# Tiefenentladeschutz.net
KiCad netlist of a schematic drawn in EAGLE
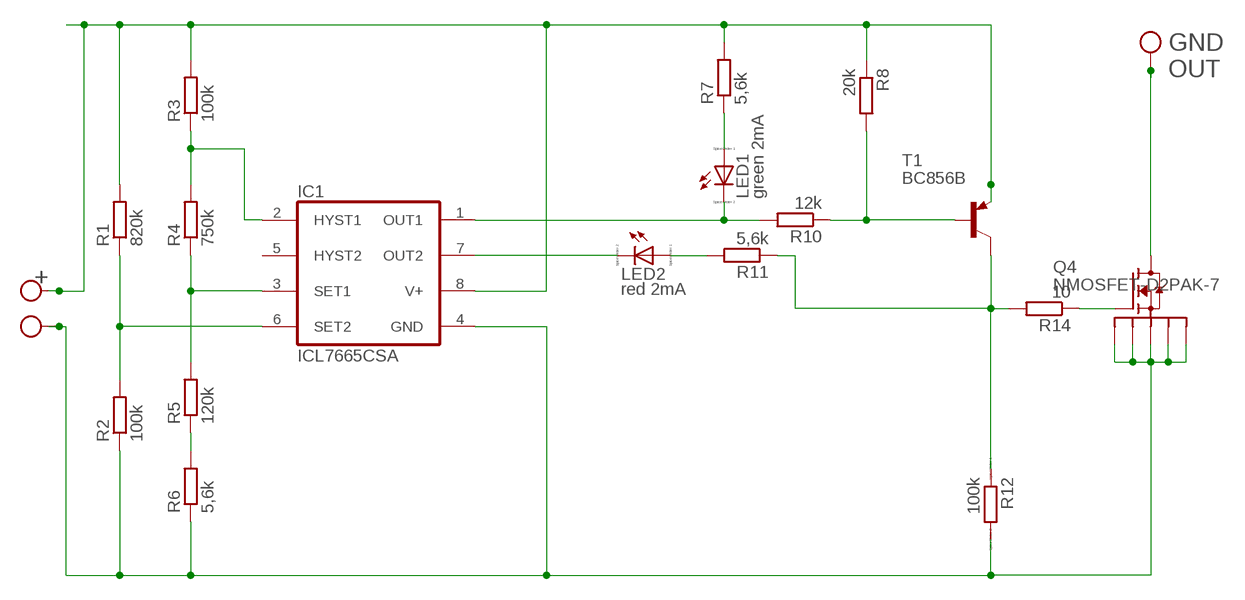
[diagram p0: schematic, sheet 1]

(export (version "E")
  (design (tool "Eeschema 10.0.6"))
  (components
    (comp (ref "IC1")
      (value "ICL7665CSA")
      (footprint "eagle-import:SO08")
      (fields (field (name "MPN") "ICL7665CSA+"))
      (libsource (lib "eagle-import") (part "ICL7665CSA"))
    )
    (comp (ref "LED1")
      (value "green 2mA")
      (footprint "eagle-import:LED_SML0603")
      (libsource (lib "eagle-import") (part "LED_ESML0603"))
    )
    (comp (ref "LED2")
      (value "red 2mA")
      (footprint "eagle-import:LED_SML0603")
      (libsource (lib "eagle-import") (part "LED_ESML0603"))
    )
    (comp (ref "Q4")
      (value "NMOSFET-D2PAK-7")
      (footprint "eagle-import:H2PAK-6")
      (libsource (lib "eagle-import") (part "NMOSFET-D2PAK-7"))
    )
    (comp (ref "R1")
      (value "820k")
      (footprint "eagle-import:R0603")
      (libsource (lib "eagle-import") (part "resistor_R-EU_R0603"))
    )
    (comp (ref "R2")
      (value "100k")
      (footprint "eagle-import:R0603")
      (libsource (lib "eagle-import") (part "resistor_R-EU_R0603"))
    )
    (comp (ref "R3")
      (value "100k")
      (footprint "eagle-import:M1206")
      (libsource (lib "eagle-import") (part "R-EU_M1206"))
    )
    (comp (ref "R4")
      (value "750k")
      (footprint "eagle-import:R0603")
      (libsource (lib "eagle-import") (part "R-EU_R0603"))
    )
    (comp (ref "R5")
      (value "120k")
      (footprint "eagle-import:R0603")
      (libsource (lib "eagle-import") (part "R-EU_R0603"))
    )
    (comp (ref "R6")
      (value "5,6k")
      (footprint "eagle-import:R0603")
      (libsource (lib "eagle-import") (part "R-EU_R0603"))
    )
    (comp (ref "R7")
      (value "5,6k")
      (footprint "eagle-import:R0603")
      (libsource (lib "eagle-import") (part "R-EU_R0603"))
    )
    (comp (ref "R8")
      (value "20k")
      (footprint "eagle-import:R0603")
      (libsource (lib "eagle-import") (part "R-EU_R0603"))
    )
    (comp (ref "R10")
      (value "12k")
      (footprint "eagle-import:R0603")
      (libsource (lib "eagle-import") (part "R-EU_R0603"))
    )
    (comp (ref "R11")
      (value "5,6k")
      (footprint "eagle-import:R0603")
      (libsource (lib "eagle-import") (part "R-EU_R0603"))
    )
    (comp (ref "R12")
      (value "100k")
      (footprint "eagle-import:R1206")
      (libsource (lib "eagle-import") (part "RR1206"))
    )
    (comp (ref "R14")
      (value "10")
      (footprint "eagle-import:R0603")
      (libsource (lib "eagle-import") (part "R-EU_R0603"))
    )
    (comp (ref "T1")
      (value "BC856B")
      (footprint "eagle-import:SOT23-BEC")
      (libsource (lib "eagle-import") (part "-PNP-SOT23-BECBC856B"))
    )
    (comp (ref "U$4")
      (value "PIN2.54")
      (footprint "eagle-import:PIN")
      (libsource (lib "eagle-import") (part "PIN2.54"))
    )
    (comp (ref "U$6")
      (value "PIN1.27")
      (footprint "eagle-import:PIN-1.27")
      (libsource (lib "eagle-import") (part "PIN1.27"))
    )
    (comp (ref "U$7")
      (value "PIN1.27")
      (footprint "eagle-import:PIN-1.27")
      (libsource (lib "eagle-import") (part "PIN1.27"))
    )
  )
  (nets
    (net (code "1") (name "Net-(IC1-GND)") (class "Default")
      (node (ref "IC1") (pin "4") (pinfunction "GND_4") (pintype "power_in"))
      (node (ref "Q4") (pin "S1") (pinfunction "S1_S1") (pintype "passive"))
      (node (ref "Q4") (pin "S2") (pinfunction "S2_S2") (pintype "passive"))
      (node (ref "Q4") (pin "S3") (pinfunction "S3_S3") (pintype "passive"))
      (node (ref "Q4") (pin "S4") (pinfunction "S4_S4") (pintype "passive"))
      (node (ref "Q4") (pin "S5") (pinfunction "S5_S5") (pintype "passive"))
      (node (ref "R12") (pin "2") (pinfunction "2_2") (pintype "passive"))
      (node (ref "R2") (pin "1") (pinfunction "1_1") (pintype "passive"))
      (node (ref "R6") (pin "1") (pinfunction "1_1") (pintype "passive"))
      (node (ref "U$6") (pin "P$1") (pinfunction "P$1_P$1") (pintype "bidirectional"))
    )
    (net (code "2") (name "Net-(IC1-HYST1)") (class "Default")
      (node (ref "IC1") (pin "2") (pinfunction "HYST1_2") (pintype "input"))
      (node (ref "R3") (pin "1") (pinfunction "1_1") (pintype "passive"))
      (node (ref "R4") (pin "2") (pinfunction "2_2") (pintype "passive"))
    )
    (net (code "3") (name "Net-(IC1-OUT1)") (class "Default")
      (node (ref "IC1") (pin "1") (pinfunction "OUT1_1") (pintype "output"))
      (node (ref "LED1") (pin "C") (pinfunction "C_C") (pintype "passive"))
      (node (ref "R10") (pin "2") (pinfunction "2_2") (pintype "passive"))
    )
    (net (code "4") (name "Net-(IC1-OUT2)") (class "Default")
      (node (ref "IC1") (pin "7") (pinfunction "OUT2_7") (pintype "output"))
      (node (ref "LED2") (pin "C") (pinfunction "C_C") (pintype "passive"))
    )
    (net (code "5") (name "Net-(IC1-SET1)") (class "Default")
      (node (ref "IC1") (pin "3") (pinfunction "SET1_3") (pintype "input"))
      (node (ref "R4") (pin "1") (pinfunction "1_1") (pintype "passive"))
      (node (ref "R5") (pin "2") (pinfunction "2_2") (pintype "passive"))
    )
    (net (code "6") (name "Net-(IC1-SET2)") (class "Default")
      (node (ref "IC1") (pin "6") (pinfunction "SET2_6") (pintype "input"))
      (node (ref "R1") (pin "1") (pinfunction "1_1") (pintype "passive"))
      (node (ref "R2") (pin "2") (pinfunction "2_2") (pintype "passive"))
    )
    (net (code "7") (name "Net-(IC1-V+)") (class "Default")
      (node (ref "IC1") (pin "8") (pinfunction "V+_8") (pintype "power_in"))
      (node (ref "R1") (pin "2") (pinfunction "2_2") (pintype "passive"))
      (node (ref "R3") (pin "2") (pinfunction "2_2") (pintype "passive"))
      (node (ref "R7") (pin "2") (pinfunction "2_2") (pintype "passive"))
      (node (ref "R8") (pin "1") (pinfunction "1_1") (pintype "passive"))
      (node (ref "T1") (pin "E") (pinfunction "E_E") (pintype "passive"))
      (node (ref "U$4") (pin "P$1") (pinfunction "P$1_P$1") (pintype "bidirectional"))
    )
    (net (code "8") (name "Net-(LED1-PadA)") (class "Default")
      (node (ref "LED1") (pin "A") (pinfunction "A_A") (pintype "passive"))
      (node (ref "R7") (pin "1") (pinfunction "1_1") (pintype "passive"))
    )
    (net (code "9") (name "Net-(LED2-PadA)") (class "Default")
      (node (ref "LED2") (pin "A") (pinfunction "A_A") (pintype "passive"))
      (node (ref "R11") (pin "2") (pinfunction "2_2") (pintype "passive"))
    )
    (net (code "10") (name "Net-(Q4-PadD)") (class "Default")
      (node (ref "Q4") (pin "D") (pinfunction "D_D") (pintype "passive"))
      (node (ref "U$7") (pin "P$1") (pinfunction "P$1_P$1") (pintype "bidirectional"))
    )
    (net (code "11") (name "Net-(Q4-PadG)") (class "Default")
      (node (ref "Q4") (pin "G") (pinfunction "G_G") (pintype "passive"))
      (node (ref "R14") (pin "1") (pinfunction "1_1") (pintype "passive"))
    )
    (net (code "12") (name "Net-(R5-Pad1)") (class "Default")
      (node (ref "R5") (pin "1") (pinfunction "1_1") (pintype "passive"))
      (node (ref "R6") (pin "2") (pinfunction "2_2") (pintype "passive"))
    )
    (net (code "13") (name "Net-(R10-Pad1)") (class "Default")
      (node (ref "R10") (pin "1") (pinfunction "1_1") (pintype "passive"))
      (node (ref "R8") (pin "2") (pinfunction "2_2") (pintype "passive"))
      (node (ref "T1") (pin "B") (pinfunction "B_B") (pintype "passive"))
    )
    (net (code "14") (name "Net-(R11-Pad1)") (class "Default")
      (node (ref "R11") (pin "1") (pinfunction "1_1") (pintype "passive"))
      (node (ref "R12") (pin "1") (pinfunction "1_1") (pintype "passive"))
      (node (ref "R14") (pin "2") (pinfunction "2_2") (pintype "passive"))
      (node (ref "T1") (pin "C") (pinfunction "C_C") (pintype "passive"))
    )
    (net (code "15") (name "unconnected-(IC1-HYST2-Pad5)") (class "Default")
      (node (ref "IC1") (pin "5") (pinfunction "HYST2_5") (pintype "input"))
    )
  )
)
